# EEG_AFE_Sheet_4.net
KiCad netlist of a schematic drawn in Altium Designer
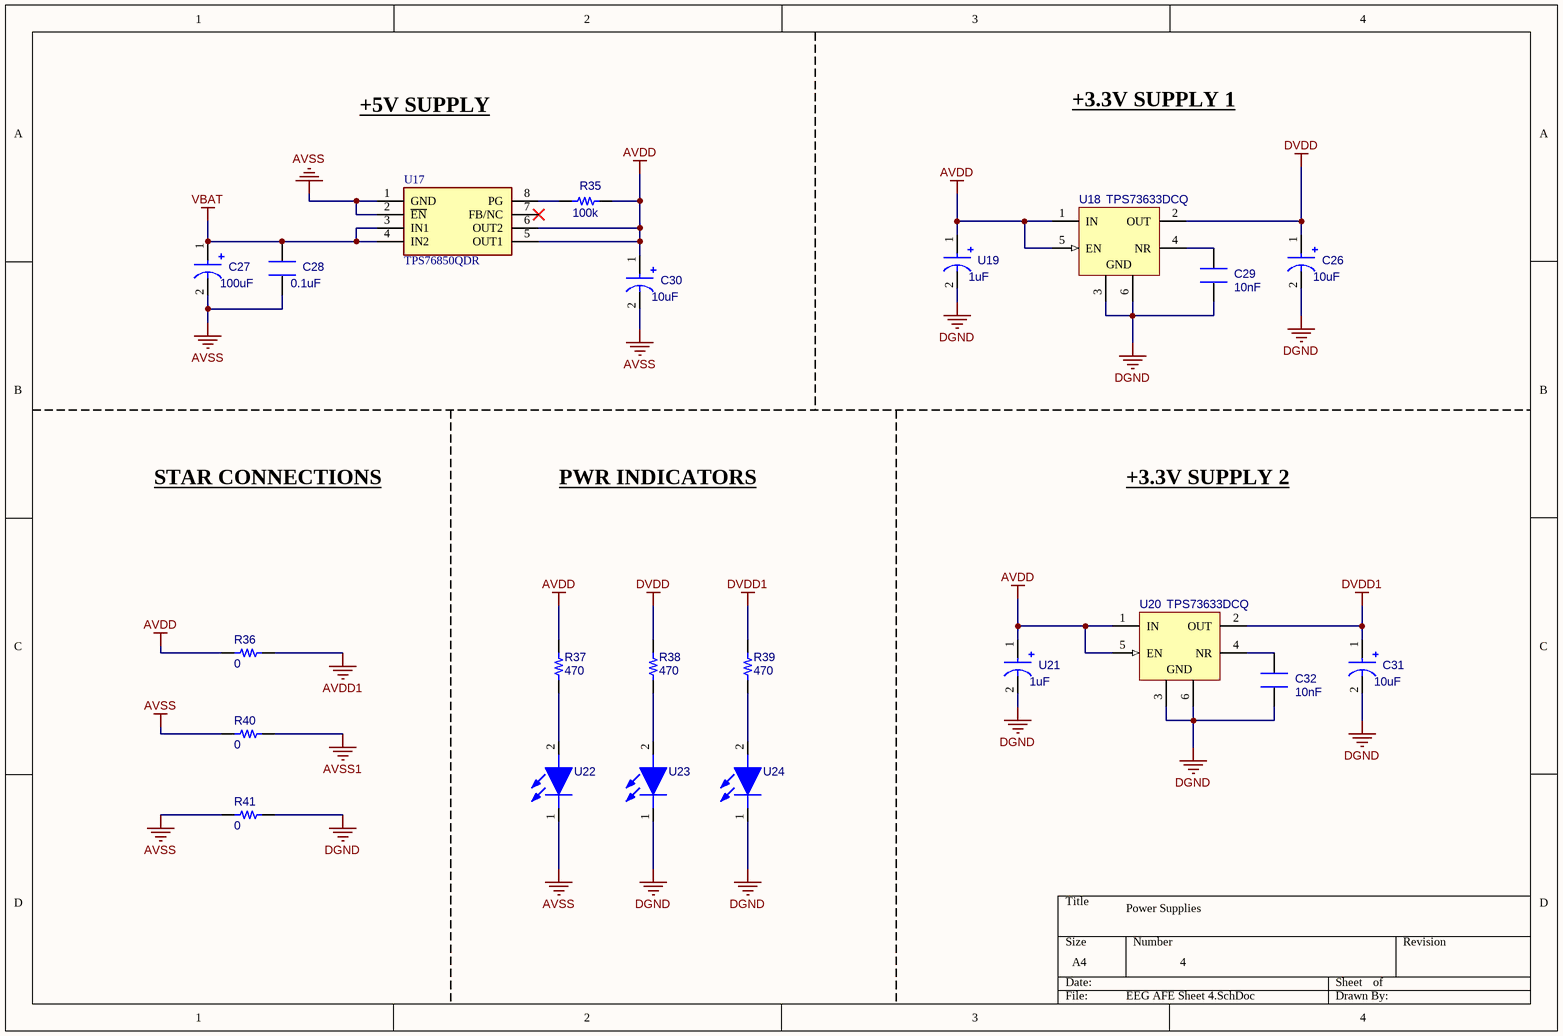
[diagram p0: EEG AFE Sheet 4.SchDoc]

(export (version "E")
  (design (tool "Eeschema 10.0.6"))
  (components
    (comp (ref "C26")
      (value "10uF")
      (footprint "CAP ALSMD ELEC 4.3MM H5.4MM")
      (fields (field (name "MANUFACTURER") "???") (field (name "MANUFACTURER PART NUMBER") "EEE-FK1E100R"))
      (libsource (lib "Schlib") (part "EEE-FK1E100R"))
    )
    (comp (ref "C27")
      (value "100uF")
      (footprint "CAP ALSMD ELEC 6.6MM H7.7MM")
      (description "WCAP-AS5H Aluminum Electrolytic Capacitors")
      (fields
        (field (name "MANUFACTURER") "???")
        (field (name "MANUFACTURER PART NUMBER") "865230345005")
        (field (name "PUBLISHER") "Paraqum Technologies")
      )
      (libsource (lib "Schlib") (part "865230345005"))
    )
    (comp (ref "C28")
      (value "0.1uF")
      (footprint "CAP 0603_1608")
      (fields (field (name "MANUFACTURER") "???") (field (name "MANUFACTURER PART NUMBER") "08055C104KAT2A"))
      (libsource (lib "Schlib") (part "08055C104KAT2A"))
    )
    (comp (ref "C29")
      (value "10nF")
      (footprint "CAP 0603_1608")
      (fields (field (name "MANUFACTURER") "???") (field (name "MANUFACTURER PART NUMBER") "08055C104KAT2A"))
      (libsource (lib "Schlib") (part "08055C104KAT2A"))
    )
    (comp (ref "C30")
      (value "10uF")
      (footprint "CAP ALSMD ELEC 4.3MM H5.4MM")
      (fields (field (name "MANUFACTURER") "???") (field (name "MANUFACTURER PART NUMBER") "EEE-FK1E100R"))
      (libsource (lib "Schlib") (part "EEE-FK1E100R"))
    )
    (comp (ref "C31")
      (value "10uF")
      (footprint "CAP ALSMD ELEC 4.3MM H5.4MM")
      (fields (field (name "MANUFACTURER") "???") (field (name "MANUFACTURER PART NUMBER") "EEE-FK1E100R"))
      (libsource (lib "Schlib") (part "EEE-FK1E100R"))
    )
    (comp (ref "C32")
      (value "10nF")
      (footprint "CAP 0603_1608")
      (fields (field (name "MANUFACTURER") "???") (field (name "MANUFACTURER PART NUMBER") "08055C104KAT2A"))
      (libsource (lib "Schlib") (part "08055C104KAT2A"))
    )
    (comp (ref "R35")
      (value "100k")
      (footprint "RES 0603_1608")
      (fields
        (field (name "MANUFACTURER") "???")
        (field (name "MANUFACTURER PART NUMBER") "RC0805FR-0710KL")
        (field (name "PUBLISHER") "Paraqum Technologies")
      )
      (libsource (lib "Schlib") (part "RC0805FR-0710KL"))
    )
    (comp (ref "R36")
      (value "0")
      (footprint "RES 0603_1608")
      (fields
        (field (name "MANUFACTURER") "???")
        (field (name "MANUFACTURER PART NUMBER") "RC0805FR-0710KL")
        (field (name "PUBLISHER") "Paraqum Technologies")
      )
      (libsource (lib "Schlib") (part "RC0805FR-0710KL"))
    )
    (comp (ref "R37")
      (value "470")
      (footprint "RES 0603_1608")
      (fields
        (field (name "MANUFACTURER") "???")
        (field (name "MANUFACTURER PART NUMBER") "RC0805FR-0710KL")
        (field (name "PUBLISHER") "Paraqum Technologies")
      )
      (libsource (lib "Schlib") (part "RC0805FR-0710KL"))
    )
    (comp (ref "R38")
      (value "470")
      (footprint "RES 0603_1608")
      (fields
        (field (name "MANUFACTURER") "???")
        (field (name "MANUFACTURER PART NUMBER") "RC0805FR-0710KL")
        (field (name "PUBLISHER") "Paraqum Technologies")
      )
      (libsource (lib "Schlib") (part "RC0805FR-0710KL"))
    )
    (comp (ref "R39")
      (value "470")
      (footprint "RES 0603_1608")
      (fields
        (field (name "MANUFACTURER") "???")
        (field (name "MANUFACTURER PART NUMBER") "RC0805FR-0710KL")
        (field (name "PUBLISHER") "Paraqum Technologies")
      )
      (libsource (lib "Schlib") (part "RC0805FR-0710KL"))
    )
    (comp (ref "R40")
      (value "0")
      (footprint "RES 0603_1608")
      (fields
        (field (name "MANUFACTURER") "???")
        (field (name "MANUFACTURER PART NUMBER") "RC0805FR-0710KL")
        (field (name "PUBLISHER") "Paraqum Technologies")
      )
      (libsource (lib "Schlib") (part "RC0805FR-0710KL"))
    )
    (comp (ref "R41")
      (value "0")
      (footprint "RES 0603_1608")
      (fields
        (field (name "MANUFACTURER") "???")
        (field (name "MANUFACTURER PART NUMBER") "RC0805FR-0710KL")
        (field (name "PUBLISHER") "Paraqum Technologies")
      )
      (libsource (lib "Schlib") (part "RC0805FR-0710KL"))
    )
    (comp (ref "U17")
      (value "TPS76850QDR")
      (footprint "SOIC127P600X175-8N")
      (description "LDO Voltage Regulators Micropower LDO Reg")
      (fields (field (name "MOUSER PART NUMBER") "595-TPS76850QDR"))
      (libsource (lib "Schlib") (part "TPS76850QDR"))
    )
    (comp (ref "U18")
      (value "TPS73633DCQ")
      (footprint "SOT127P706X180-6N")
      (description "Fixed Positive LDO Regulator, 3.3V, 0.2V Dropout, BICMOS, PDSO6")
      (fields (field (name "MANUFACTURER") "???") (field (name "PUBLISHER") "Paraqum Technologies"))
      (libsource (lib "Schlib") (part "TPS73633DCQ"))
    )
    (comp (ref "U19")
      (value "1uF")
      (footprint "CAPC0805_TANT")
      (fields
        (field (name "MANUFACTURER") "???")
        (field (name "MANUFACTURER PART NUMBER") "TPSR105K025R4000")
        (field (name "PUBLISHER") "Paraqum Technologies")
      )
      (libsource (lib "Schlib") (part "TPSR105K025R4000"))
    )
    (comp (ref "U20")
      (value "TPS73633DCQ")
      (footprint "SOT127P706X180-6N")
      (description "Fixed Positive LDO Regulator, 3.3V, 0.2V Dropout, BICMOS, PDSO6")
      (fields (field (name "MANUFACTURER") "???") (field (name "PUBLISHER") "Paraqum Technologies"))
      (libsource (lib "Schlib") (part "TPS73633DCQ"))
    )
    (comp (ref "U21")
      (value "1uF")
      (footprint "CAPC0805_TANT")
      (fields
        (field (name "MANUFACTURER") "???")
        (field (name "MANUFACTURER PART NUMBER") "TPSR105K025R4000")
        (field (name "PUBLISHER") "Paraqum Technologies")
      )
      (libsource (lib "Schlib") (part "TPSR105K025R4000"))
    )
    (comp (ref "U22")
      (value "*")
      (footprint "LEDC2012X80N")
      (description "Single Color LED, Blue, Water Clear, 1.4mm")
      (fields
        (field (name "MANUFACTURER") "???")
        (field (name "MANUFACTURER PART NUMBER") "150080BS75000")
        (field (name "PUBLISHER") "Paraqum Technologies")
      )
      (libsource (lib "Schlib") (part "150080BS75000"))
    )
    (comp (ref "U23")
      (value "*")
      (footprint "LEDC2012X80N")
      (description "Single Color LED, Blue, Water Clear, 1.4mm")
      (fields
        (field (name "MANUFACTURER") "???")
        (field (name "MANUFACTURER PART NUMBER") "150080BS75000")
        (field (name "PUBLISHER") "Paraqum Technologies")
      )
      (libsource (lib "Schlib") (part "150080BS75000"))
    )
    (comp (ref "U24")
      (value "*")
      (footprint "LEDC2012X80N")
      (description "Single Color LED, Blue, Water Clear, 1.4mm")
      (fields
        (field (name "MANUFACTURER") "???")
        (field (name "MANUFACTURER PART NUMBER") "150080BS75000")
        (field (name "PUBLISHER") "Paraqum Technologies")
      )
      (libsource (lib "Schlib") (part "150080BS75000"))
    )
  )
  (nets
    (net (code "1") (name "AVDD") (class "Default")
      (node (ref "C30") (pin "1") (pinfunction "C_1") (pintype "passive"))
      (node (ref "R35") (pin "1") (pinfunction "1_1") (pintype "passive"))
      (node (ref "R36") (pin "2") (pinfunction "2_2") (pintype "passive"))
      (node (ref "R37") (pin "2") (pinfunction "2_2") (pintype "passive"))
      (node (ref "U17") (pin "5") (pinfunction "OUT1_5") (pintype "passive"))
      (node (ref "U17") (pin "6") (pinfunction "OUT2_6") (pintype "passive"))
      (node (ref "U18") (pin "1") (pinfunction "IN_1") (pintype "power_in"))
      (node (ref "U18") (pin "5") (pinfunction "EN_5") (pintype "input"))
      (node (ref "U19") (pin "1") (pinfunction "C_1") (pintype "passive"))
      (node (ref "U20") (pin "1") (pinfunction "IN_1") (pintype "power_in"))
      (node (ref "U20") (pin "5") (pinfunction "EN_5") (pintype "input"))
      (node (ref "U21") (pin "1") (pinfunction "C_1") (pintype "passive"))
    )
    (net (code "2") (name "AVDD1") (class "Default")
      (node (ref "R36") (pin "1") (pinfunction "1_1") (pintype "passive"))
    )
    (net (code "3") (name "AVSS") (class "Default")
      (node (ref "C27") (pin "2") (pinfunction "A_2") (pintype "passive"))
      (node (ref "C28") (pin "1") (pinfunction "1_1") (pintype "passive"))
      (node (ref "C30") (pin "2") (pinfunction "A_2") (pintype "passive"))
      (node (ref "R40") (pin "2") (pinfunction "2_2") (pintype "passive"))
      (node (ref "R41") (pin "2") (pinfunction "2_2") (pintype "passive"))
      (node (ref "U17") (pin "1") (pinfunction "GND_1") (pintype "passive"))
      (node (ref "U17") (pin "2") (pinfunction "~{EN}_2") (pintype "passive"))
      (node (ref "U22") (pin "1") (pinfunction "K_1") (pintype "passive"))
    )
    (net (code "4") (name "AVSS1") (class "Default")
      (node (ref "R40") (pin "1") (pinfunction "1_1") (pintype "passive"))
    )
    (net (code "5") (name "DGND") (class "Default")
      (node (ref "C26") (pin "2") (pinfunction "A_2") (pintype "passive"))
      (node (ref "C29") (pin "1") (pinfunction "1_1") (pintype "passive"))
      (node (ref "C31") (pin "2") (pinfunction "A_2") (pintype "passive"))
      (node (ref "C32") (pin "1") (pinfunction "1_1") (pintype "passive"))
      (node (ref "R41") (pin "1") (pinfunction "1_1") (pintype "passive"))
      (node (ref "U18") (pin "3") (pinfunction "GND_3") (pintype "power_in"))
      (node (ref "U18") (pin "6") (pinfunction "GND_6") (pintype "power_in"))
      (node (ref "U19") (pin "2") (pinfunction "A_2") (pintype "passive"))
      (node (ref "U20") (pin "3") (pinfunction "GND_3") (pintype "power_in"))
      (node (ref "U20") (pin "6") (pinfunction "GND_6") (pintype "power_in"))
      (node (ref "U21") (pin "2") (pinfunction "A_2") (pintype "passive"))
      (node (ref "U23") (pin "1") (pinfunction "K_1") (pintype "passive"))
      (node (ref "U24") (pin "1") (pinfunction "K_1") (pintype "passive"))
    )
    (net (code "6") (name "DVDD") (class "Default")
      (node (ref "C26") (pin "1") (pinfunction "C_1") (pintype "passive"))
      (node (ref "R38") (pin "2") (pinfunction "2_2") (pintype "passive"))
      (node (ref "U18") (pin "2") (pinfunction "OUT_2") (pintype "power_in"))
    )
    (net (code "7") (name "DVDD1") (class "Default")
      (node (ref "C31") (pin "1") (pinfunction "C_1") (pintype "passive"))
      (node (ref "R39") (pin "2") (pinfunction "2_2") (pintype "passive"))
      (node (ref "U20") (pin "2") (pinfunction "OUT_2") (pintype "power_in"))
    )
    (net (code "8") (name "Net-(U17-PG)") (class "Default")
      (node (ref "R35") (pin "2") (pinfunction "2_2") (pintype "passive"))
      (node (ref "U17") (pin "8") (pinfunction "PG_8") (pintype "passive"))
    )
    (net (code "9") (name "Net-(U18-NR)") (class "Default")
      (node (ref "C29") (pin "2") (pinfunction "2_2") (pintype "passive"))
      (node (ref "U18") (pin "4") (pinfunction "NR_4") (pintype "passive"))
    )
    (net (code "10") (name "Net-(U20-NR)") (class "Default")
      (node (ref "C32") (pin "2") (pinfunction "2_2") (pintype "passive"))
      (node (ref "U20") (pin "4") (pinfunction "NR_4") (pintype "passive"))
    )
    (net (code "11") (name "Net-(U22-A)") (class "Default")
      (node (ref "R37") (pin "1") (pinfunction "1_1") (pintype "passive"))
      (node (ref "U22") (pin "2") (pinfunction "A_2") (pintype "passive"))
    )
    (net (code "12") (name "Net-(U23-A)") (class "Default")
      (node (ref "R38") (pin "1") (pinfunction "1_1") (pintype "passive"))
      (node (ref "U23") (pin "2") (pinfunction "A_2") (pintype "passive"))
    )
    (net (code "13") (name "Net-(U24-A)") (class "Default")
      (node (ref "R39") (pin "1") (pinfunction "1_1") (pintype "passive"))
      (node (ref "U24") (pin "2") (pinfunction "A_2") (pintype "passive"))
    )
    (net (code "14") (name "VBAT") (class "Default")
      (node (ref "C27") (pin "1") (pinfunction "C_1") (pintype "passive"))
      (node (ref "C28") (pin "2") (pinfunction "2_2") (pintype "passive"))
      (node (ref "U17") (pin "3") (pinfunction "IN1_3") (pintype "passive"))
      (node (ref "U17") (pin "4") (pinfunction "IN2_4") (pintype "passive"))
    )
    (net (code "15") (name "unconnected-(U17-FB{slash}NC-Pad7)") (class "Default")
      (node (ref "U17") (pin "7") (pinfunction "FB/NC_7") (pintype "passive+no_connect"))
    )
  )
)
